# EasyEDA_project.net
KiCad netlist of a schematic drawn in EasyEDA
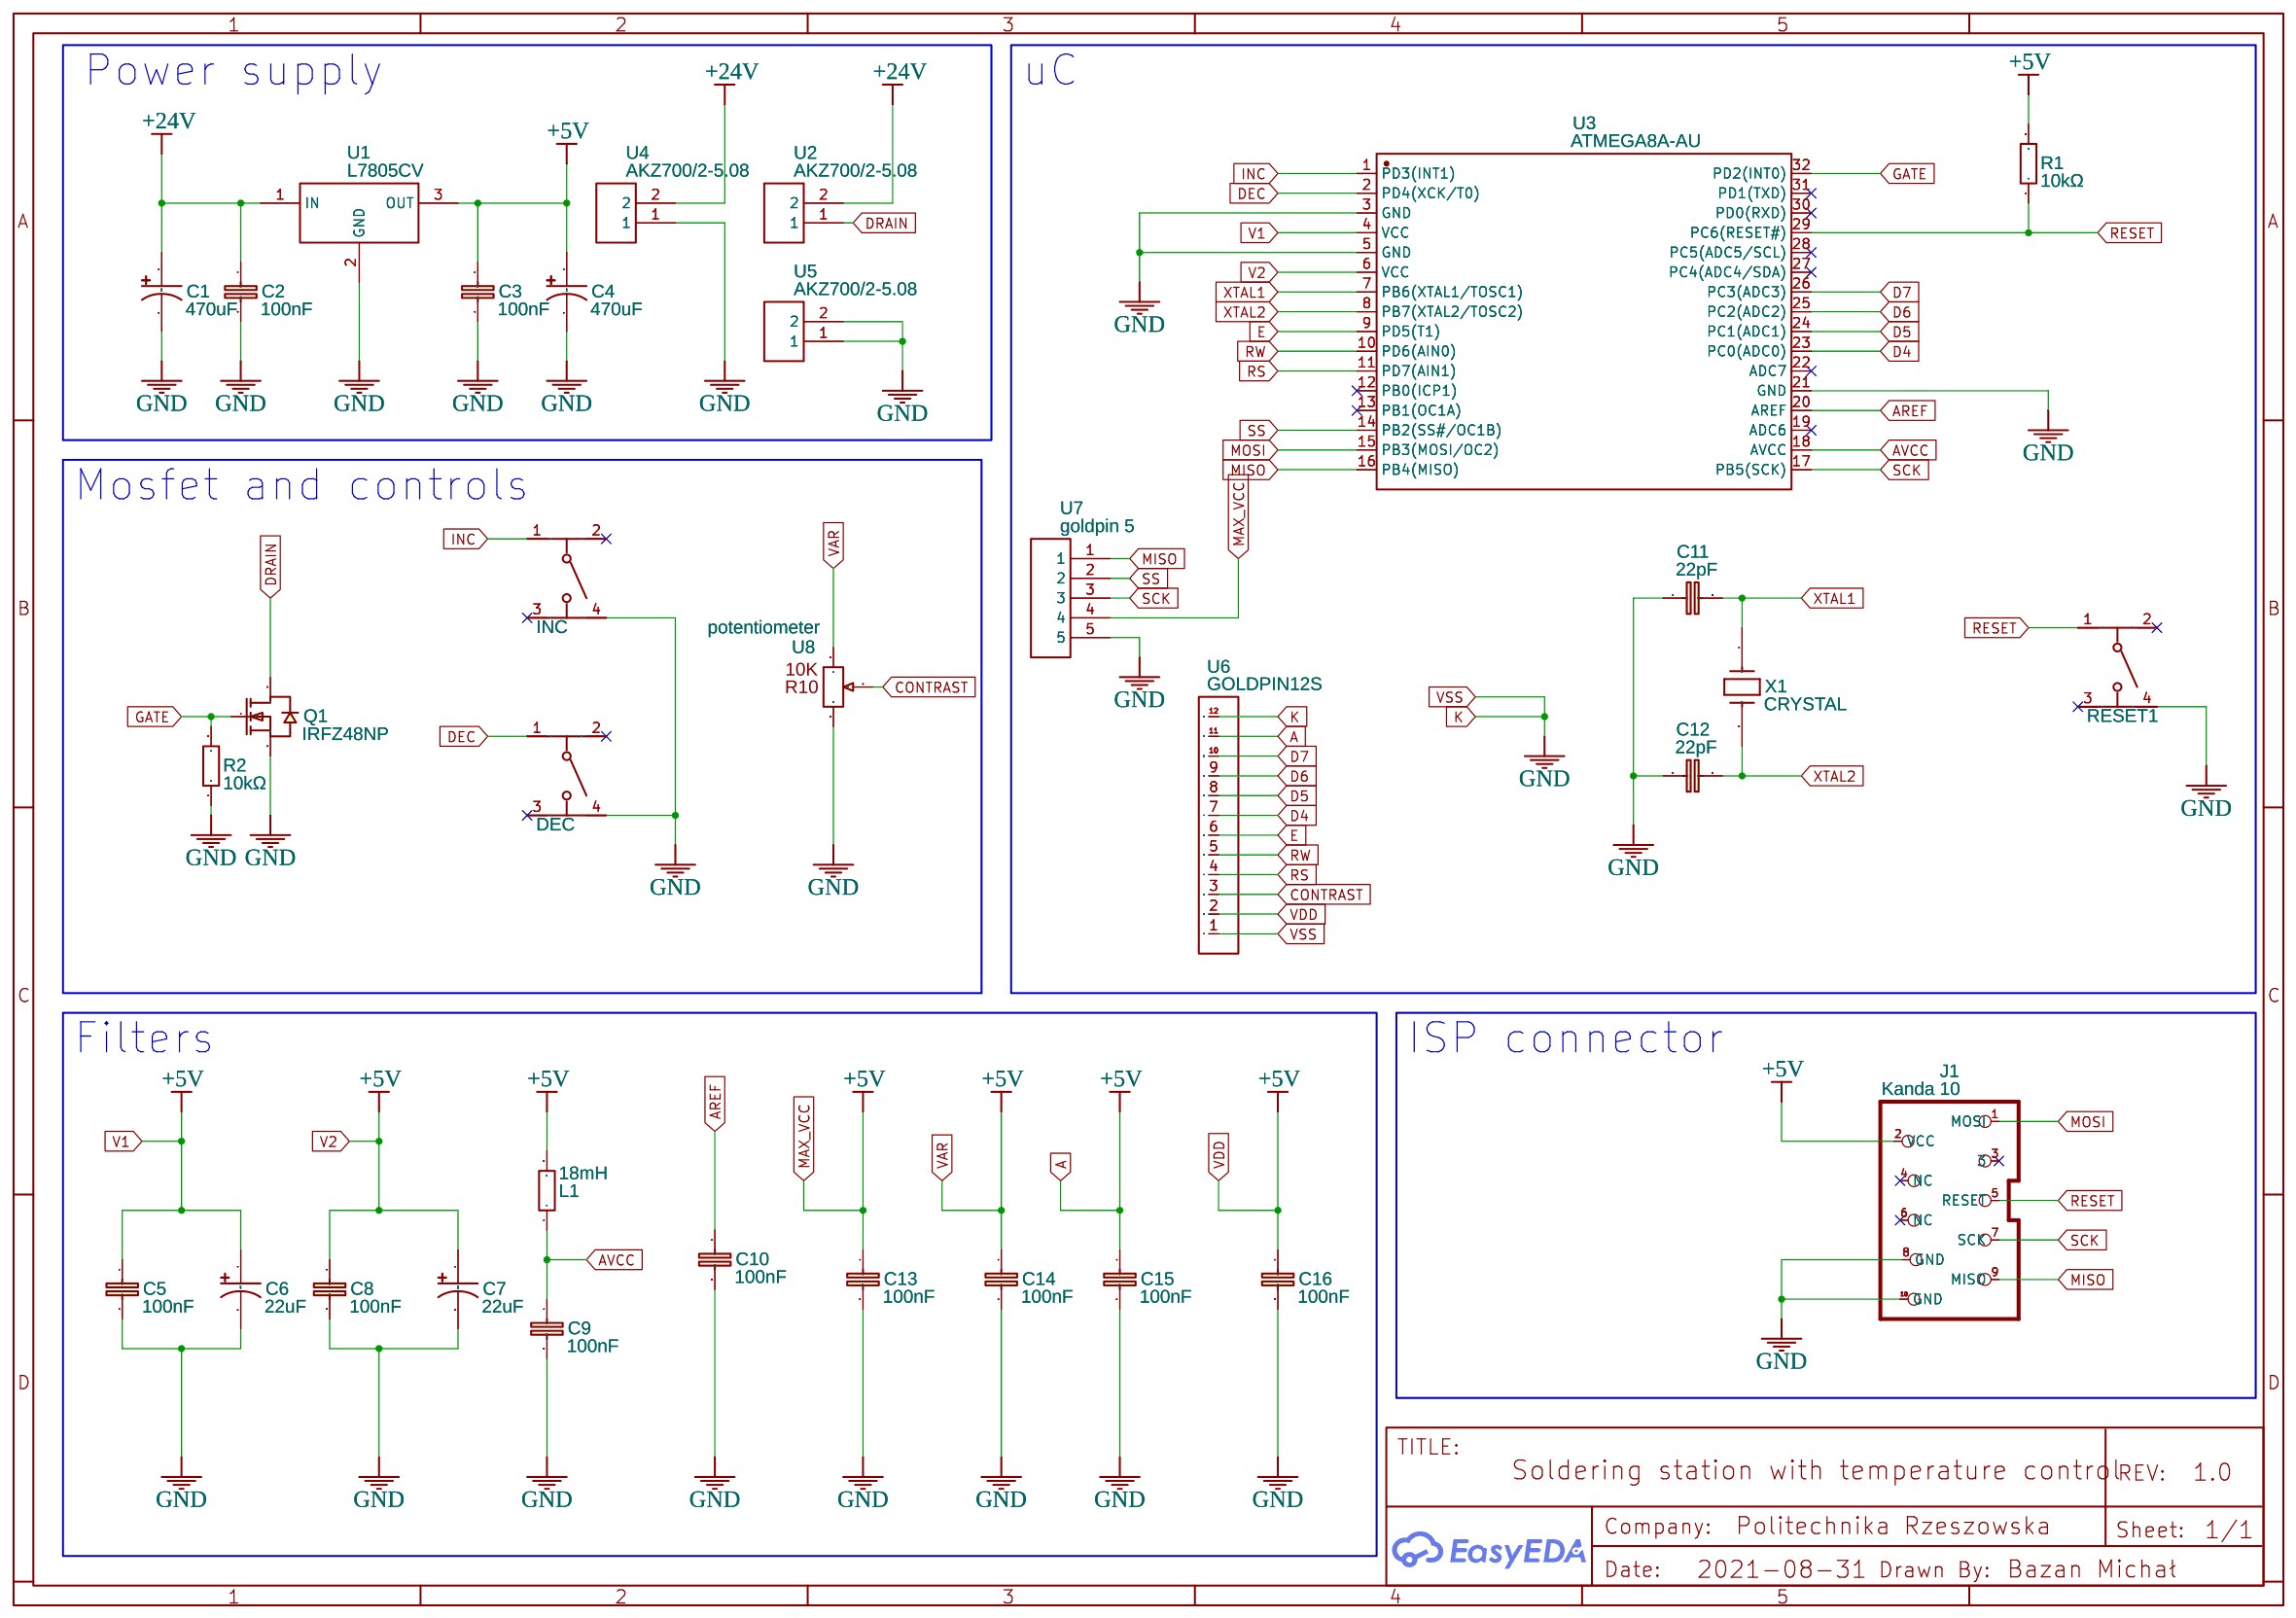
[diagram p0: schematic sheet]

(export (version "E")
  (design (tool "Eeschema 10.0.6"))
  (components
    (comp (ref "C1")
      (value "470uF")
      (fields
        (field (name "BOM_Manufacturer Part") "UWD1E471MCL1GS")
        (field (name "BOM_Supplier Part") "C251022")
      )
      (libsource (lib "") (part "UWD1E471MCL1GS"))
    )
    (comp (ref "C2") (value "100nF") (libsource (lib "") (part "CAP1206")))
    (comp (ref "C3") (value "100nF") (libsource (lib "") (part "CAP1206")))
    (comp (ref "C4")
      (value "470uF")
      (fields
        (field (name "BOM_Manufacturer Part") "UWD1E471MCL1GS")
        (field (name "BOM_Supplier Part") "C251022")
      )
      (libsource (lib "") (part "UWD1E471MCL1GS_1"))
    )
    (comp (ref "C5") (value "100nF") (libsource (lib "") (part "CAP1206")))
    (comp (ref "C6")
      (value "22uF")
      (fields
        (field (name "BOM_Manufacturer Part") "EEHZC1K220P")
        (field (name "BOM_Supplier Part") "C178647")
      )
      (libsource (lib "") (part "EEHZC1K220P"))
    )
    (comp (ref "C7")
      (value "22uF")
      (fields
        (field (name "BOM_Manufacturer Part") "EEHZC1K220P")
        (field (name "BOM_Supplier Part") "C178647")
      )
      (libsource (lib "") (part "EEHZC1K220P"))
    )
    (comp (ref "C8") (value "100nF") (libsource (lib "") (part "CAP1206")))
    (comp (ref "C9") (value "100nF") (libsource (lib "") (part "CAP1206")))
    (comp (ref "C10") (value "100nF") (libsource (lib "") (part "CAP1206")))
    (comp (ref "C11") (value "22pF") (libsource (lib "") (part "CAP1206_1")))
    (comp (ref "C12") (value "22pF") (libsource (lib "") (part "CAP1206_2")))
    (comp (ref "C13") (value "100nF") (libsource (lib "") (part "CAP1206")))
    (comp (ref "C14") (value "100nF") (libsource (lib "") (part "CAP1206")))
    (comp (ref "C15") (value "100nF") (libsource (lib "") (part "CAP1206")))
    (comp (ref "C16") (value "100nF") (libsource (lib "") (part "CAP1206")))
    (comp (ref "DEC")
      (value "Switch-6x6x7.3-square-head")
      (fields
        (field (name "BOM_Manufacturer Part") "Switch,6*6*7.3Plastic square head,260G, 0.25mm,Straight line")
        (field (name "BOM_Supplier Part") "C71843")
      )
      (libsource (lib "") (part "Switch-6x6x7.3-square-head_2"))
    )
    (comp (ref "INC")
      (value "Switch-6x6x7.3-square-head")
      (fields
        (field (name "BOM_Manufacturer Part") "Switch,6*6*7.3Plastic square head,260G, 0.25mm,Straight line")
        (field (name "BOM_Supplier Part") "C71843")
      )
      (libsource (lib "") (part "Switch-6x6x7.3-square-head_1"))
    )
    (comp (ref "J1") (value "Kanda 10") (libsource (lib "") (part "Kanda 10")))
    (comp (ref "L1")
      (value "18mH")
      (fields (field (name "BOM_Manufacturer Part") "1623925-3") (field (name "BOM_Supplier Part") "C306261"))
      (libsource (lib "") (part "1623925-3"))
    )
    (comp (ref "Q1")
      (value "IRFZ48NP")
      (fields (field (name "BOM_Supplier Part") "C878808"))
      (libsource (lib "") (part "IRFZ48NP"))
    )
    (comp (ref "R1")
      (value "10kΩ")
      (fields
        (field (name "BOM_Manufacturer Part") "RTT062702FTP")
        (field (name "BOM_Supplier Part") "undefined")
      )
      (libsource (lib "") (part "27KΩ"))
    )
    (comp (ref "R2")
      (value "10kΩ")
      (fields
        (field (name "BOM_Manufacturer Part") "RTT062702FTP")
        (field (name "BOM_Supplier Part") "undefined")
      )
      (libsource (lib "") (part "27KΩ"))
    )
    (comp (ref "RESET1")
      (value "Switch-6x6x7.3-square-head")
      (fields
        (field (name "BOM_Manufacturer Part") "Switch,6*6*7.3Plastic square head,260G, 0.25mm,Straight line")
        (field (name "BOM_Supplier Part") "C71843")
      )
      (libsource (lib "") (part "Switch-6x6x7.3-square-head"))
    )
    (comp (ref "U1")
      (value "L7805CV")
      (fields (field (name "BOM_Supplier Part") "C111887"))
      (libsource (lib "") (part "L7805CV"))
    )
    (comp (ref "U2") (value "AKZ700/2-5.08") (libsource (lib "") (part "AKZ700/2-5.08")))
    (comp (ref "U3")
      (value "ATMEGA8A-AU")
      (fields (field (name "BOM_Supplier Part") "C16190"))
      (libsource (lib "") (part "ATMEGA8A-AU"))
    )
    (comp (ref "U4") (value "AKZ700/2-5.08") (libsource (lib "") (part "AKZ700/2-5.08")))
    (comp (ref "U5") (value "AKZ700/2-5.08") (libsource (lib "") (part "AKZ700/2-5.08")))
    (comp (ref "U6")
      (value "GOLDPIN12S")
      (fields (field (name "BOM_Manufacturer Part") "New SchematicLib"))
      (libsource (lib "") (part "GOLDPIN12S"))
    )
    (comp (ref "U7") (value "goldpin 5") (libsource (lib "") (part "goldpin 5")))
    (comp (ref "U8") (value "potentiometer") (libsource (lib "") (part "potentiometer")))
    (comp (ref "X1") (value "CRYSTAL") (libsource (lib "") (part "CRYSTAL")))
  )
  (nets
    (net (code "1") (name "+24V") (class "Default")
      (node (ref "C1") (pin "1") (pinfunction "1_1") (pintype "unspecified"))
      (node (ref "C2") (pin "1") (pinfunction "1_1") (pintype "unspecified"))
      (node (ref "U1") (pin "1") (pinfunction "IN_1") (pintype "passive"))
      (node (ref "U2") (pin "2") (pinfunction "2_2") (pintype "unspecified"))
      (node (ref "U4") (pin "2") (pinfunction "2_2") (pintype "unspecified"))
    )
    (net (code "2") (name "A") (class "Default")
      (node (ref "C13") (pin "1") (pinfunction "1_1") (pintype "unspecified"))
      (node (ref "C14") (pin "1") (pinfunction "1_1") (pintype "unspecified"))
      (node (ref "C15") (pin "1") (pinfunction "1_1") (pintype "unspecified"))
      (node (ref "C16") (pin "1") (pinfunction "1_1") (pintype "unspecified"))
      (node (ref "C3") (pin "1") (pinfunction "1_1") (pintype "unspecified"))
      (node (ref "C4") (pin "1") (pinfunction "1_1") (pintype "unspecified"))
      (node (ref "C5") (pin "1") (pinfunction "1_1") (pintype "unspecified"))
      (node (ref "C6") (pin "1") (pinfunction "1_1") (pintype "unspecified"))
      (node (ref "C7") (pin "1") (pinfunction "1_1") (pintype "unspecified"))
      (node (ref "C8") (pin "1") (pinfunction "1_1") (pintype "unspecified"))
      (node (ref "J1") (pin "2") (pinfunction "VCC_2") (pintype "unspecified"))
      (node (ref "L1") (pin "2") (pinfunction "2_2") (pintype "unspecified"))
      (node (ref "R1") (pin "2") (pinfunction "2_2") (pintype "input"))
      (node (ref "U1") (pin "3") (pinfunction "OUT_3") (pintype "passive"))
      (node (ref "U3") (pin "4") (pinfunction "VCC_4") (pintype "unspecified"))
      (node (ref "U3") (pin "6") (pinfunction "VCC_6") (pintype "unspecified"))
      (node (ref "U6") (pin "11") (pinfunction "11_11") (pintype "unspecified"))
      (node (ref "U6") (pin "2") (pinfunction "2_2") (pintype "unspecified"))
      (node (ref "U7") (pin "4") (pinfunction "4_4") (pintype "unspecified"))
      (node (ref "U8") (pin "1") (pinfunction "1_1") (pintype "input"))
    )
    (net (code "3") (name "AREF") (class "Default")
      (node (ref "C10") (pin "1") (pinfunction "1_1") (pintype "unspecified"))
      (node (ref "U3") (pin "20") (pinfunction "AREF_20") (pintype "unspecified"))
    )
    (net (code "4") (name "AVCC") (class "Default")
      (node (ref "C9") (pin "1") (pinfunction "1_1") (pintype "unspecified"))
      (node (ref "L1") (pin "1") (pinfunction "1_1") (pintype "unspecified"))
      (node (ref "U3") (pin "18") (pinfunction "AVCC_18") (pintype "unspecified"))
    )
    (net (code "5") (name "CONTRAST") (class "Default")
      (node (ref "U6") (pin "3") (pinfunction "3_3") (pintype "unspecified"))
      (node (ref "U8") (pin "2") (pinfunction "2_2") (pintype "input"))
    )
    (net (code "6") (name "D4") (class "Default")
      (node (ref "U3") (pin "23") (pinfunction "PC0(ADC0)_23") (pintype "unspecified"))
      (node (ref "U6") (pin "7") (pinfunction "7_7") (pintype "unspecified"))
    )
    (net (code "7") (name "D5") (class "Default")
      (node (ref "U3") (pin "24") (pinfunction "PC1(ADC1)_24") (pintype "unspecified"))
      (node (ref "U6") (pin "8") (pinfunction "8_8") (pintype "unspecified"))
    )
    (net (code "8") (name "D6") (class "Default")
      (node (ref "U3") (pin "25") (pinfunction "PC2(ADC2)_25") (pintype "unspecified"))
      (node (ref "U6") (pin "9") (pinfunction "9_9") (pintype "unspecified"))
    )
    (net (code "9") (name "D7") (class "Default")
      (node (ref "U3") (pin "26") (pinfunction "PC3(ADC3)_26") (pintype "unspecified"))
      (node (ref "U6") (pin "10") (pinfunction "10_10") (pintype "unspecified"))
    )
    (net (code "10") (name "DEC") (class "Default")
      (node (ref "DEC") (pin "1") (pinfunction "1_1") (pintype "unspecified"))
      (node (ref "U3") (pin "2") (pinfunction "PD4(XCK/T0)_2") (pintype "unspecified"))
    )
    (net (code "11") (name "DRAIN") (class "Default")
      (node (ref "Q1") (pin "2") (pinfunction "D_2") (pintype "unspecified"))
      (node (ref "U2") (pin "1") (pinfunction "1_1") (pintype "unspecified"))
    )
    (net (code "12") (name "E") (class "Default")
      (node (ref "U3") (pin "9") (pinfunction "PD5(T1)_9") (pintype "unspecified"))
      (node (ref "U6") (pin "6") (pinfunction "6_6") (pintype "unspecified"))
    )
    (net (code "13") (name "GATE") (class "Default")
      (node (ref "Q1") (pin "1") (pinfunction "G_1") (pintype "unspecified"))
      (node (ref "R2") (pin "2") (pinfunction "2_2") (pintype "input"))
      (node (ref "U3") (pin "32") (pinfunction "PD2(INT0)_32") (pintype "unspecified"))
    )
    (net (code "14") (name "INC") (class "Default")
      (node (ref "INC") (pin "1") (pinfunction "1_1") (pintype "unspecified"))
      (node (ref "U3") (pin "1") (pinfunction "PD3(INT1)_1") (pintype "unspecified"))
    )
    (net (code "15") (name "K") (class "Default")
      (node (ref "C1") (pin "2") (pinfunction "2_2") (pintype "unspecified"))
      (node (ref "C10") (pin "2") (pinfunction "2_2") (pintype "unspecified"))
      (node (ref "C11") (pin "1") (pinfunction "1_1") (pintype "unspecified"))
      (node (ref "C12") (pin "2") (pinfunction "2_2") (pintype "unspecified"))
      (node (ref "C13") (pin "2") (pinfunction "2_2") (pintype "unspecified"))
      (node (ref "C14") (pin "2") (pinfunction "2_2") (pintype "unspecified"))
      (node (ref "C15") (pin "2") (pinfunction "2_2") (pintype "unspecified"))
      (node (ref "C16") (pin "2") (pinfunction "2_2") (pintype "unspecified"))
      (node (ref "C2") (pin "2") (pinfunction "2_2") (pintype "unspecified"))
      (node (ref "C3") (pin "2") (pinfunction "2_2") (pintype "unspecified"))
      (node (ref "C4") (pin "2") (pinfunction "2_2") (pintype "unspecified"))
      (node (ref "C5") (pin "2") (pinfunction "2_2") (pintype "unspecified"))
      (node (ref "C6") (pin "2") (pinfunction "2_2") (pintype "unspecified"))
      (node (ref "C7") (pin "2") (pinfunction "2_2") (pintype "unspecified"))
      (node (ref "C8") (pin "2") (pinfunction "2_2") (pintype "unspecified"))
      (node (ref "C9") (pin "2") (pinfunction "2_2") (pintype "unspecified"))
      (node (ref "DEC") (pin "4") (pinfunction "4_4") (pintype "unspecified"))
      (node (ref "INC") (pin "4") (pinfunction "4_4") (pintype "unspecified"))
      (node (ref "J1") (pin "10") (pinfunction "GND_10") (pintype "unspecified"))
      (node (ref "J1") (pin "8") (pinfunction "GND_8") (pintype "unspecified"))
      (node (ref "Q1") (pin "3") (pinfunction "S_3") (pintype "unspecified"))
      (node (ref "R2") (pin "1") (pinfunction "1_1") (pintype "input"))
      (node (ref "RESET1") (pin "4") (pinfunction "4_4") (pintype "unspecified"))
      (node (ref "U1") (pin "2") (pinfunction "GND_2") (pintype "passive"))
      (node (ref "U3") (pin "21") (pinfunction "GND_21") (pintype "unspecified"))
      (node (ref "U3") (pin "3") (pinfunction "GND_3") (pintype "unspecified"))
      (node (ref "U3") (pin "5") (pinfunction "GND_5") (pintype "unspecified"))
      (node (ref "U4") (pin "1") (pinfunction "1_1") (pintype "unspecified"))
      (node (ref "U5") (pin "1") (pinfunction "1_1") (pintype "unspecified"))
      (node (ref "U5") (pin "2") (pinfunction "2_2") (pintype "unspecified"))
      (node (ref "U6") (pin "1") (pinfunction "1_1") (pintype "unspecified"))
      (node (ref "U6") (pin "12") (pinfunction "12_12") (pintype "unspecified"))
      (node (ref "U7") (pin "5") (pinfunction "5_5") (pintype "unspecified"))
      (node (ref "U8") (pin "3") (pinfunction "3_3") (pintype "input"))
    )
    (net (code "16") (name "MISO") (class "Default")
      (node (ref "J1") (pin "9") (pinfunction "MISO_9") (pintype "unspecified"))
      (node (ref "U3") (pin "16") (pinfunction "PB4(MISO)_16") (pintype "unspecified"))
      (node (ref "U7") (pin "1") (pinfunction "1_1") (pintype "unspecified"))
    )
    (net (code "17") (name "MOSI") (class "Default")
      (node (ref "J1") (pin "1") (pinfunction "MOSI_1") (pintype "unspecified"))
      (node (ref "U3") (pin "15") (pinfunction "PB3(MOSI/OC2)_15") (pintype "unspecified"))
    )
    (net (code "18") (name "RESET") (class "Default")
      (node (ref "J1") (pin "5") (pinfunction "RESET_5") (pintype "unspecified"))
      (node (ref "R1") (pin "1") (pinfunction "1_1") (pintype "input"))
      (node (ref "RESET1") (pin "1") (pinfunction "1_1") (pintype "unspecified"))
      (node (ref "U3") (pin "29") (pinfunction "PC6(RESET#)_29") (pintype "unspecified"))
    )
    (net (code "19") (name "RS") (class "Default")
      (node (ref "U3") (pin "11") (pinfunction "PD7(AIN1)_11") (pintype "unspecified"))
      (node (ref "U6") (pin "4") (pinfunction "4_4") (pintype "unspecified"))
    )
    (net (code "20") (name "RW") (class "Default")
      (node (ref "U3") (pin "10") (pinfunction "PD6(AIN0)_10") (pintype "unspecified"))
      (node (ref "U6") (pin "5") (pinfunction "5_5") (pintype "unspecified"))
    )
    (net (code "21") (name "SCK") (class "Default")
      (node (ref "J1") (pin "7") (pinfunction "SCK_7") (pintype "unspecified"))
      (node (ref "U3") (pin "17") (pinfunction "PB5(SCK)_17") (pintype "unspecified"))
      (node (ref "U7") (pin "3") (pinfunction "3_3") (pintype "unspecified"))
    )
    (net (code "22") (name "SS") (class "Default")
      (node (ref "U3") (pin "14") (pinfunction "PB2(SS#/OC1B)_14") (pintype "unspecified"))
      (node (ref "U7") (pin "2") (pinfunction "2_2") (pintype "unspecified"))
    )
    (net (code "23") (name "XTAL1") (class "Default")
      (node (ref "C11") (pin "2") (pinfunction "2_2") (pintype "unspecified"))
      (node (ref "U3") (pin "7") (pinfunction "PB6(XTAL1/TOSC1)_7") (pintype "unspecified"))
      (node (ref "X1") (pin "1") (pinfunction "1_1") (pintype "unspecified"))
    )
    (net (code "24") (name "XTAL2") (class "Default")
      (node (ref "C12") (pin "1") (pinfunction "1_1") (pintype "unspecified"))
      (node (ref "U3") (pin "8") (pinfunction "PB7(XTAL2/TOSC2)_8") (pintype "unspecified"))
      (node (ref "X1") (pin "2") (pinfunction "2_2") (pintype "unspecified"))
    )
    (net (code "25") (name "unconnected-(DEC-Pad2)") (class "Default")
      (node (ref "DEC") (pin "2") (pinfunction "2_2") (pintype "unspecified+no_connect"))
    )
    (net (code "26") (name "unconnected-(DEC-Pad3)") (class "Default")
      (node (ref "DEC") (pin "3") (pinfunction "3_3") (pintype "unspecified+no_connect"))
    )
    (net (code "27") (name "unconnected-(INC-Pad2)") (class "Default")
      (node (ref "INC") (pin "2") (pinfunction "2_2") (pintype "unspecified+no_connect"))
    )
    (net (code "28") (name "unconnected-(INC-Pad3)") (class "Default")
      (node (ref "INC") (pin "3") (pinfunction "3_3") (pintype "unspecified+no_connect"))
    )
    (net (code "29") (name "unconnected-(J1-NC-Pad4)") (class "Default")
      (node (ref "J1") (pin "4") (pinfunction "NC_4") (pintype "unspecified+no_connect"))
    )
    (net (code "30") (name "unconnected-(J1-NC-Pad6)") (class "Default")
      (node (ref "J1") (pin "6") (pinfunction "NC_6") (pintype "unspecified+no_connect"))
    )
    (net (code "31") (name "unconnected-(J1-Pad3)") (class "Default")
      (node (ref "J1") (pin "3") (pinfunction "3_3") (pintype "unspecified+no_connect"))
    )
    (net (code "32") (name "unconnected-(RESET1-Pad2)") (class "Default")
      (node (ref "RESET1") (pin "2") (pinfunction "2_2") (pintype "unspecified+no_connect"))
    )
    (net (code "33") (name "unconnected-(RESET1-Pad3)") (class "Default")
      (node (ref "RESET1") (pin "3") (pinfunction "3_3") (pintype "unspecified+no_connect"))
    )
    (net (code "34") (name "unconnected-(U3-ADC6-Pad19)") (class "Default")
      (node (ref "U3") (pin "19") (pinfunction "ADC6_19") (pintype "unspecified+no_connect"))
    )
    (net (code "35") (name "unconnected-(U3-ADC7-Pad22)") (class "Default")
      (node (ref "U3") (pin "22") (pinfunction "ADC7_22") (pintype "unspecified+no_connect"))
    )
    (net (code "36") (name "unconnected-(U3-PB0(ICP1)-Pad12)") (class "Default")
      (node (ref "U3") (pin "12") (pinfunction "PB0(ICP1)_12") (pintype "unspecified+no_connect"))
    )
    (net (code "37") (name "unconnected-(U3-PB1(OC1A)-Pad13)") (class "Default")
      (node (ref "U3") (pin "13") (pinfunction "PB1(OC1A)_13") (pintype "unspecified+no_connect"))
    )
    (net (code "38") (name "unconnected-(U3-PC4(ADC4{slash}SDA)-Pad27)") (class "Default")
      (node (ref "U3") (pin "27") (pinfunction "PC4(ADC4/SDA)_27") (pintype "unspecified+no_connect"))
    )
    (net (code "39") (name "unconnected-(U3-PC5(ADC5{slash}SCL)-Pad28)") (class "Default")
      (node (ref "U3") (pin "28") (pinfunction "PC5(ADC5/SCL)_28") (pintype "unspecified+no_connect"))
    )
    (net (code "40") (name "unconnected-(U3-PD0(RXD)-Pad30)") (class "Default")
      (node (ref "U3") (pin "30") (pinfunction "PD0(RXD)_30") (pintype "unspecified+no_connect"))
    )
    (net (code "41") (name "unconnected-(U3-PD1(TXD)-Pad31)") (class "Default")
      (node (ref "U3") (pin "31") (pinfunction "PD1(TXD)_31") (pintype "unspecified+no_connect"))
    )
  )
)
